# LED-PCB_DIG2.net
KiCad netlist of a schematic drawn in Altium Designer
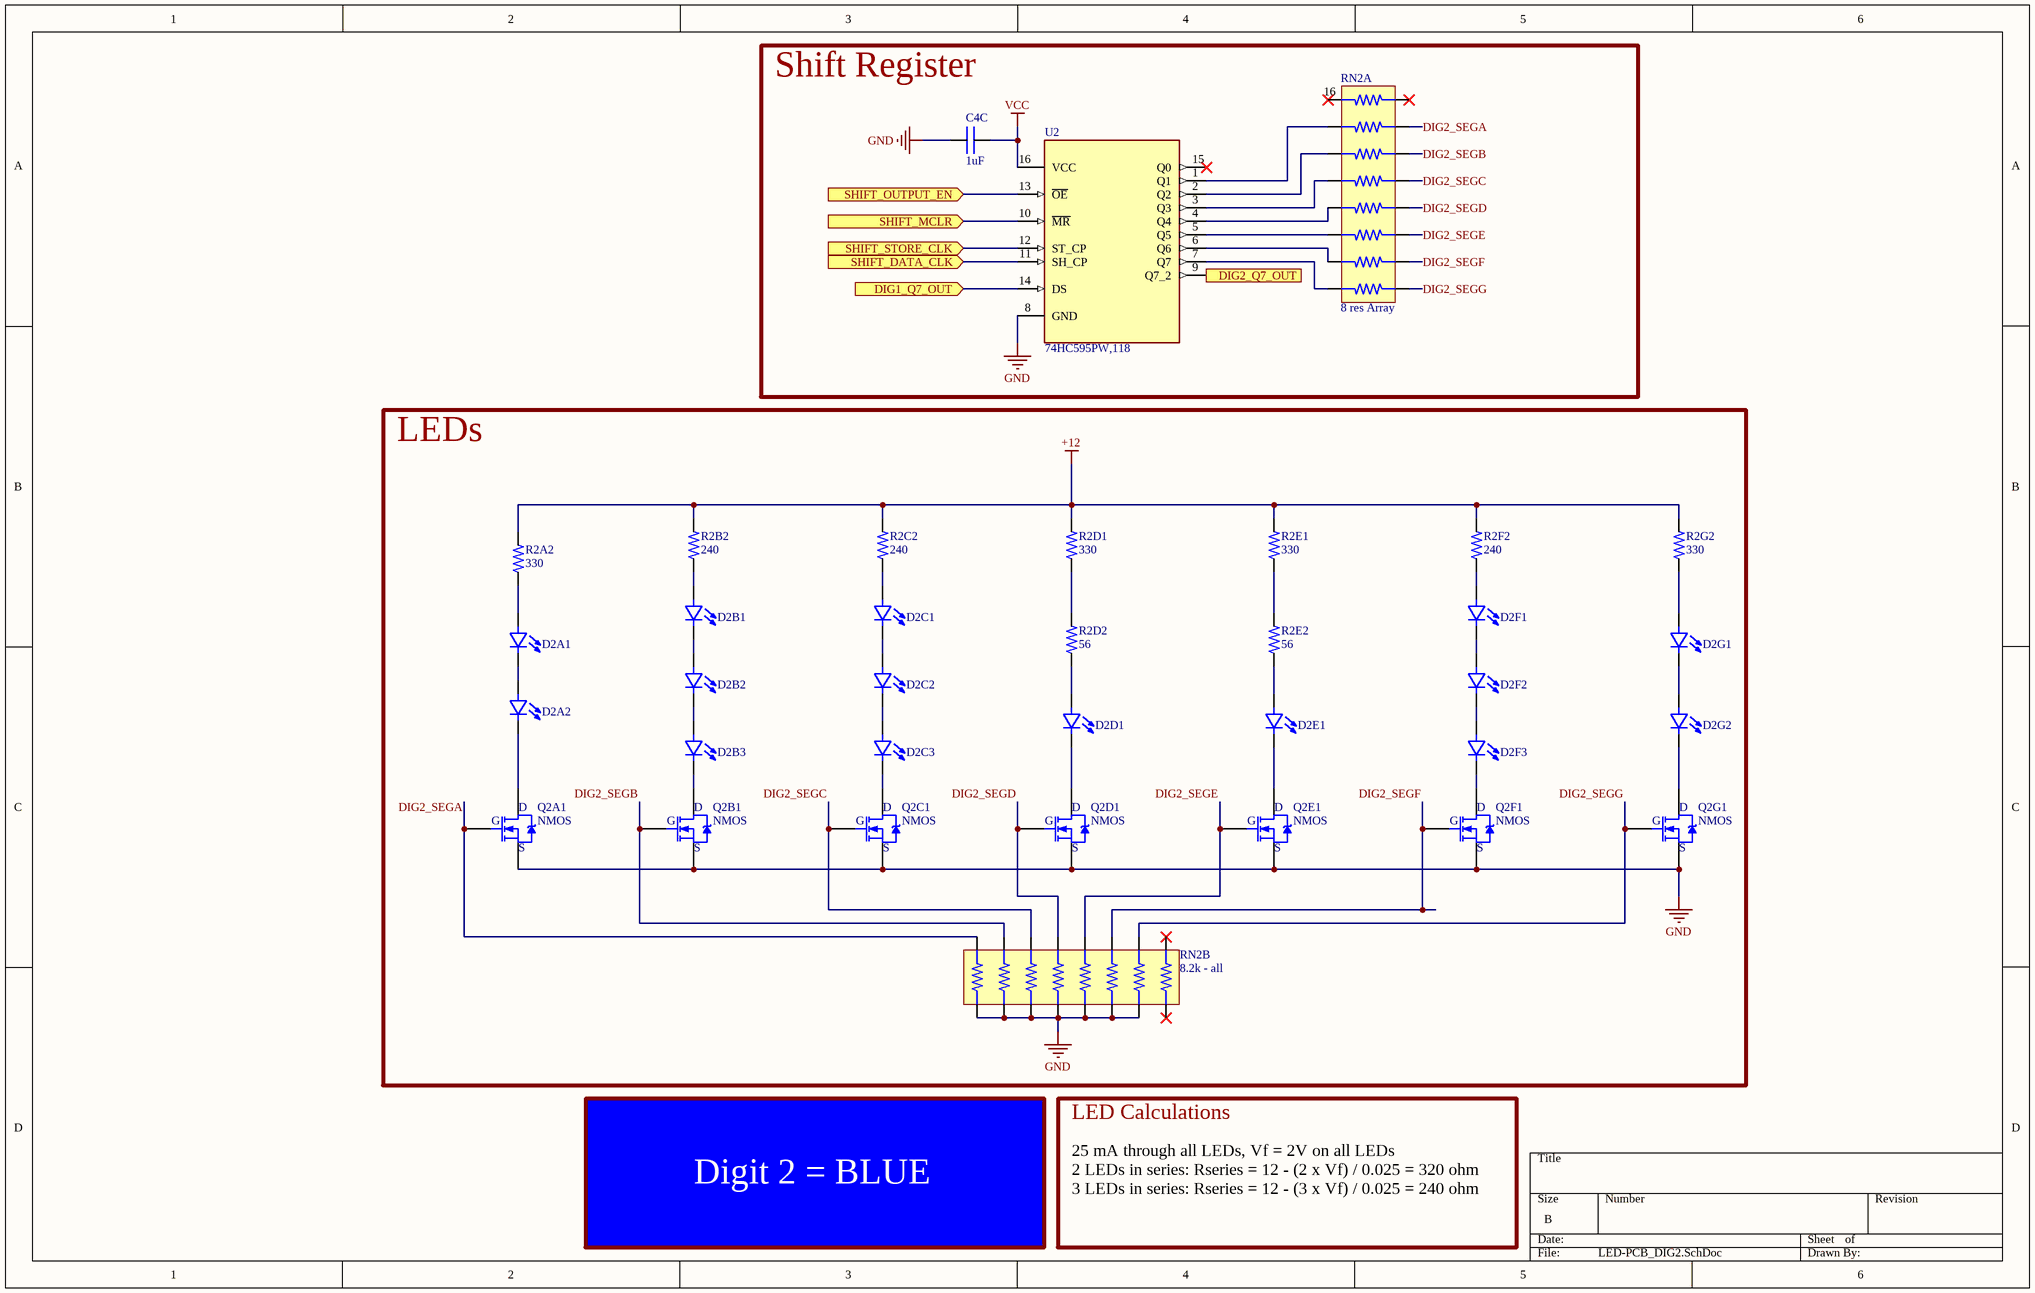
[diagram p0: LED-PCB_DIG2.SchDoc]

(export (version "E")
  (design (tool "Eeschema 10.0.6"))
  (components
    (comp (ref "C4C")
      (value "1uF")
      (footprint "sinking-clock:0402 CAP")
      (description "Capaicitor")
      (fields (field (name "MFR") "Samsung Microelectronics") (field (name "Comment") "CAP"))
      (libsource (lib "sinking-clock") (part "CAP"))
    )
    (comp (ref "D2A1")
      (value "LED - single")
      (footprint "sinking-clock:LED - 0603")
      (fields (field (name "MFR") "Wurth Elektronik"))
      (libsource (lib "sinking-clock") (part "LED - single"))
    )
    (comp (ref "D2A2")
      (value "LED - single")
      (footprint "sinking-clock:LED - 0603")
      (fields (field (name "MFR") "Wurth Elektronik"))
      (libsource (lib "sinking-clock") (part "LED - single"))
    )
    (comp (ref "D2B1")
      (value "LED - single")
      (footprint "sinking-clock:LED - 0603")
      (fields (field (name "MFR") "Wurth Elektronik"))
      (libsource (lib "sinking-clock") (part "LED - single"))
    )
    (comp (ref "D2B2")
      (value "LED - single")
      (footprint "sinking-clock:LED - 0603")
      (fields (field (name "MFR") "Wurth Elektronik"))
      (libsource (lib "sinking-clock") (part "LED - single"))
    )
    (comp (ref "D2B3")
      (value "LED - single")
      (footprint "sinking-clock:LED - 0603")
      (fields (field (name "MFR") "Wurth Elektronik"))
      (libsource (lib "sinking-clock") (part "LED - single"))
    )
    (comp (ref "D2C1")
      (value "LED - single")
      (footprint "sinking-clock:LED - 0603")
      (fields (field (name "MFR") "Wurth Elektronik"))
      (libsource (lib "sinking-clock") (part "LED - single"))
    )
    (comp (ref "D2C2")
      (value "LED - single")
      (footprint "sinking-clock:LED - 0603")
      (fields (field (name "MFR") "Wurth Elektronik"))
      (libsource (lib "sinking-clock") (part "LED - single"))
    )
    (comp (ref "D2C3")
      (value "LED - single")
      (footprint "sinking-clock:LED - 0603")
      (fields (field (name "MFR") "Wurth Elektronik"))
      (libsource (lib "sinking-clock") (part "LED - single"))
    )
    (comp (ref "D2D1")
      (value "LED - single")
      (footprint "sinking-clock:LED - 0603")
      (fields (field (name "MFR") "Wurth Elektronik"))
      (libsource (lib "sinking-clock") (part "LED - single"))
    )
    (comp (ref "D2E1")
      (value "LED - single")
      (footprint "sinking-clock:LED - 0603")
      (fields (field (name "MFR") "Wurth Elektronik"))
      (libsource (lib "sinking-clock") (part "LED - single"))
    )
    (comp (ref "D2F1")
      (value "LED - single")
      (footprint "sinking-clock:LED - 0603")
      (fields (field (name "MFR") "Wurth Elektronik"))
      (libsource (lib "sinking-clock") (part "LED - single"))
    )
    (comp (ref "D2F2")
      (value "LED - single")
      (footprint "sinking-clock:LED - 0603")
      (fields (field (name "MFR") "Wurth Elektronik"))
      (libsource (lib "sinking-clock") (part "LED - single"))
    )
    (comp (ref "D2F3")
      (value "LED - single")
      (footprint "sinking-clock:LED - 0603")
      (fields (field (name "MFR") "Wurth Elektronik"))
      (libsource (lib "sinking-clock") (part "LED - single"))
    )
    (comp (ref "D2G1")
      (value "LED - single")
      (footprint "sinking-clock:LED - 0603")
      (fields (field (name "MFR") "Wurth Elektronik"))
      (libsource (lib "sinking-clock") (part "LED - single"))
    )
    (comp (ref "D2G2")
      (value "LED - single")
      (footprint "sinking-clock:LED - 0603")
      (fields (field (name "MFR") "Wurth Elektronik"))
      (libsource (lib "sinking-clock") (part "LED - single"))
    )
    (comp (ref "Q2A1")
      (value "NMOS")
      (footprint "sinking-clock:SOT-23")
      (description "N-Channel MOSFET")
      (fields (field (name "MFR") "Diodes Incorporated"))
      (libsource (lib "sinking-clock") (part "NMOS"))
    )
    (comp (ref "Q2B1")
      (value "NMOS")
      (footprint "sinking-clock:SOT-23")
      (description "N-Channel MOSFET")
      (fields (field (name "MFR") "Diodes Incorporated"))
      (libsource (lib "sinking-clock") (part "NMOS"))
    )
    (comp (ref "Q2C1")
      (value "NMOS")
      (footprint "sinking-clock:SOT-23")
      (description "N-Channel MOSFET")
      (fields (field (name "MFR") "Diodes Incorporated"))
      (libsource (lib "sinking-clock") (part "NMOS"))
    )
    (comp (ref "Q2D1")
      (value "NMOS")
      (footprint "sinking-clock:SOT-23")
      (description "N-Channel MOSFET")
      (fields (field (name "MFR") "Diodes Incorporated"))
      (libsource (lib "sinking-clock") (part "NMOS"))
    )
    (comp (ref "Q2E1")
      (value "NMOS")
      (footprint "sinking-clock:SOT-23")
      (description "N-Channel MOSFET")
      (fields (field (name "MFR") "Diodes Incorporated"))
      (libsource (lib "sinking-clock") (part "NMOS"))
    )
    (comp (ref "Q2F1")
      (value "NMOS")
      (footprint "sinking-clock:SOT-23")
      (description "N-Channel MOSFET")
      (fields (field (name "MFR") "Diodes Incorporated"))
      (libsource (lib "sinking-clock") (part "NMOS"))
    )
    (comp (ref "Q2G1")
      (value "NMOS")
      (footprint "sinking-clock:SOT-23")
      (description "N-Channel MOSFET")
      (fields (field (name "MFR") "Diodes Incorporated"))
      (libsource (lib "sinking-clock") (part "NMOS"))
    )
    (comp (ref "R2A2")
      (value "330")
      (footprint "sinking-clock:0402 RES")
      (description "Resistor")
      (fields (field (name "MFR") "YAGEO") (field (name "Comment") "RES"))
      (libsource (lib "sinking-clock") (part "RES"))
    )
    (comp (ref "R2B2")
      (value "240")
      (footprint "sinking-clock:0402 RES")
      (description "Resistor")
      (fields (field (name "MFR") "YAGEO") (field (name "Comment") "RES"))
      (libsource (lib "sinking-clock") (part "RES"))
    )
    (comp (ref "R2C2")
      (value "240")
      (footprint "sinking-clock:0402 RES")
      (description "Resistor")
      (fields (field (name "MFR") "YAGEO") (field (name "Comment") "RES"))
      (libsource (lib "sinking-clock") (part "RES"))
    )
    (comp (ref "R2D1")
      (value "330")
      (footprint "sinking-clock:0402 RES")
      (description "Resistor")
      (fields (field (name "MFR") "YAGEO") (field (name "Comment") "RES"))
      (libsource (lib "sinking-clock") (part "RES"))
    )
    (comp (ref "R2D2")
      (value "56")
      (footprint "sinking-clock:0402 RES")
      (description "Resistor")
      (fields (field (name "MFR") "YAGEO") (field (name "Comment") "RES"))
      (libsource (lib "sinking-clock") (part "RES"))
    )
    (comp (ref "R2E1")
      (value "330")
      (footprint "sinking-clock:0402 RES")
      (description "Resistor")
      (fields (field (name "MFR") "YAGEO") (field (name "Comment") "RES"))
      (libsource (lib "sinking-clock") (part "RES"))
    )
    (comp (ref "R2E2")
      (value "56")
      (footprint "sinking-clock:0402 RES")
      (description "Resistor")
      (fields (field (name "MFR") "YAGEO") (field (name "Comment") "RES"))
      (libsource (lib "sinking-clock") (part "RES"))
    )
    (comp (ref "R2F2")
      (value "240")
      (footprint "sinking-clock:0402 RES")
      (description "Resistor")
      (fields (field (name "MFR") "YAGEO") (field (name "Comment") "RES"))
      (libsource (lib "sinking-clock") (part "RES"))
    )
    (comp (ref "R2G2")
      (value "330")
      (footprint "sinking-clock:0402 RES")
      (description "Resistor")
      (fields (field (name "MFR") "YAGEO") (field (name "Comment") "RES"))
      (libsource (lib "sinking-clock") (part "RES"))
    )
    (comp (ref "RN2A")
      (value "8 res Array")
      (footprint "sinking-clock:EXB2HV331JV")
      (fields (field (name "MFR") "Panasonic Microelectronics"))
      (libsource (lib "sinking-clock") (part "8 res Array"))
    )
    (comp (ref "RN2B")
      (value "8.2k - all")
      (footprint "sinking-clock:MNR18ERAPJ822")
      (fields (field (name "MFR") "Rohm Semiconductor"))
      (libsource (lib "sinking-clock") (part "MNR18ERAPJ822"))
    )
    (comp (ref "U2")
      (value "74HC595PW,118")
      (footprint "sinking-clock:16-TSSOP")
      (description "Shift Shift Register 1 Element 8 Bit 16-TSSOP")
      (libsource (lib "sinking-clock") (part "74HC595PW,118"))
    )
  )
  (nets
    (net (code "1") (name "+12") (class "Default")
      (node (ref "R2A2") (pin "2") (pinfunction "2_2") (pintype "passive"))
      (node (ref "R2B2") (pin "2") (pinfunction "2_2") (pintype "passive"))
      (node (ref "R2C2") (pin "2") (pinfunction "2_2") (pintype "passive"))
      (node (ref "R2D1") (pin "2") (pinfunction "2_2") (pintype "passive"))
      (node (ref "R2E1") (pin "2") (pinfunction "2_2") (pintype "passive"))
      (node (ref "R2F2") (pin "2") (pinfunction "2_2") (pintype "passive"))
      (node (ref "R2G2") (pin "2") (pinfunction "2_2") (pintype "passive"))
    )
    (net (code "2") (name "/DIG1_Q7_OUT") (class "Default")
      (node (ref "U2") (pin "14") (pinfunction "DS_14") (pintype "input"))
    )
    (net (code "3") (name "/DIG2_Q7_OUT") (class "Default")
      (node (ref "U2") (pin "9") (pinfunction "Q7_2_9") (pintype "output"))
    )
    (net (code "4") (name "/DIG2_SEGA") (class "Default")
      (node (ref "Q2A1") (pin "1") (pinfunction "G_1") (pintype "passive"))
      (node (ref "RN2A") (pin "2") (pinfunction "2_2") (pintype "passive"))
      (node (ref "RN2B") (pin "16") (pinfunction "16_16") (pintype "passive"))
    )
    (net (code "5") (name "/DIG2_SEGB") (class "Default")
      (node (ref "Q2B1") (pin "1") (pinfunction "G_1") (pintype "passive"))
      (node (ref "RN2A") (pin "3") (pinfunction "3_3") (pintype "passive"))
      (node (ref "RN2B") (pin "15") (pinfunction "15_15") (pintype "passive"))
    )
    (net (code "6") (name "/DIG2_SEGC") (class "Default")
      (node (ref "Q2C1") (pin "1") (pinfunction "G_1") (pintype "passive"))
      (node (ref "RN2A") (pin "4") (pinfunction "4_4") (pintype "passive"))
      (node (ref "RN2B") (pin "14") (pinfunction "14_14") (pintype "passive"))
    )
    (net (code "7") (name "/DIG2_SEGD") (class "Default")
      (node (ref "Q2D1") (pin "1") (pinfunction "G_1") (pintype "passive"))
      (node (ref "RN2A") (pin "5") (pinfunction "5_5") (pintype "passive"))
      (node (ref "RN2B") (pin "13") (pinfunction "13_13") (pintype "passive"))
    )
    (net (code "8") (name "/DIG2_SEGE") (class "Default")
      (node (ref "Q2E1") (pin "1") (pinfunction "G_1") (pintype "passive"))
      (node (ref "RN2A") (pin "6") (pinfunction "6_6") (pintype "passive"))
      (node (ref "RN2B") (pin "12") (pinfunction "12_12") (pintype "passive"))
    )
    (net (code "9") (name "/DIG2_SEGF") (class "Default")
      (node (ref "Q2F1") (pin "1") (pinfunction "G_1") (pintype "passive"))
      (node (ref "RN2A") (pin "7") (pinfunction "7_7") (pintype "passive"))
      (node (ref "RN2B") (pin "11") (pinfunction "11_11") (pintype "passive"))
    )
    (net (code "10") (name "/DIG2_SEGG") (class "Default")
      (node (ref "Q2G1") (pin "1") (pinfunction "G_1") (pintype "passive"))
      (node (ref "RN2A") (pin "8") (pinfunction "8_8") (pintype "passive"))
      (node (ref "RN2B") (pin "10") (pinfunction "10_10") (pintype "passive"))
    )
    (net (code "11") (name "/SHIFT_DATA_CLK") (class "Default")
      (node (ref "U2") (pin "11") (pinfunction "SH_CP_11") (pintype "input"))
    )
    (net (code "12") (name "/SHIFT_MCLR") (class "Default")
      (node (ref "U2") (pin "10") (pinfunction "~{MR}_10") (pintype "input"))
    )
    (net (code "13") (name "/SHIFT_OUTPUT_EN") (class "Default")
      (node (ref "U2") (pin "13") (pinfunction "~{OE}_13") (pintype "input"))
    )
    (net (code "14") (name "/SHIFT_STORE_CLK") (class "Default")
      (node (ref "U2") (pin "12") (pinfunction "ST_CP_12") (pintype "input"))
    )
    (net (code "15") (name "GND") (class "Default")
      (node (ref "C4C") (pin "1") (pinfunction "1_1") (pintype "passive"))
      (node (ref "Q2A1") (pin "2") (pinfunction "S_2") (pintype "passive"))
      (node (ref "Q2B1") (pin "2") (pinfunction "S_2") (pintype "passive"))
      (node (ref "Q2C1") (pin "2") (pinfunction "S_2") (pintype "passive"))
      (node (ref "Q2D1") (pin "2") (pinfunction "S_2") (pintype "passive"))
      (node (ref "Q2E1") (pin "2") (pinfunction "S_2") (pintype "passive"))
      (node (ref "Q2F1") (pin "2") (pinfunction "S_2") (pintype "passive"))
      (node (ref "Q2G1") (pin "2") (pinfunction "S_2") (pintype "passive"))
      (node (ref "RN2B") (pin "1") (pinfunction "1_1") (pintype "passive"))
      (node (ref "RN2B") (pin "2") (pinfunction "2_2") (pintype "passive"))
      (node (ref "RN2B") (pin "3") (pinfunction "3_3") (pintype "passive"))
      (node (ref "RN2B") (pin "4") (pinfunction "4_4") (pintype "passive"))
      (node (ref "RN2B") (pin "5") (pinfunction "5_5") (pintype "passive"))
      (node (ref "RN2B") (pin "6") (pinfunction "6_6") (pintype "passive"))
      (node (ref "RN2B") (pin "7") (pinfunction "7_7") (pintype "passive"))
      (node (ref "U2") (pin "8") (pinfunction "GND_8") (pintype "passive"))
    )
    (net (code "16") (name "Net-(D2A1-A)") (class "Default")
      (node (ref "D2A1") (pin "1") (pinfunction "A_1") (pintype "passive"))
      (node (ref "R2A2") (pin "1") (pinfunction "1_1") (pintype "passive"))
    )
    (net (code "17") (name "Net-(D2A1-C)") (class "Default")
      (node (ref "D2A1") (pin "2") (pinfunction "C_2") (pintype "passive"))
      (node (ref "D2A2") (pin "1") (pinfunction "A_1") (pintype "passive"))
    )
    (net (code "18") (name "Net-(D2A2-C)") (class "Default")
      (node (ref "D2A2") (pin "2") (pinfunction "C_2") (pintype "passive"))
      (node (ref "Q2A1") (pin "3") (pinfunction "D_3") (pintype "passive"))
    )
    (net (code "19") (name "Net-(D2B1-A)") (class "Default")
      (node (ref "D2B1") (pin "1") (pinfunction "A_1") (pintype "passive"))
      (node (ref "R2B2") (pin "1") (pinfunction "1_1") (pintype "passive"))
    )
    (net (code "20") (name "Net-(D2B1-C)") (class "Default")
      (node (ref "D2B1") (pin "2") (pinfunction "C_2") (pintype "passive"))
      (node (ref "D2B2") (pin "1") (pinfunction "A_1") (pintype "passive"))
    )
    (net (code "21") (name "Net-(D2B2-C)") (class "Default")
      (node (ref "D2B2") (pin "2") (pinfunction "C_2") (pintype "passive"))
      (node (ref "D2B3") (pin "1") (pinfunction "A_1") (pintype "passive"))
    )
    (net (code "22") (name "Net-(D2B3-C)") (class "Default")
      (node (ref "D2B3") (pin "2") (pinfunction "C_2") (pintype "passive"))
      (node (ref "Q2B1") (pin "3") (pinfunction "D_3") (pintype "passive"))
    )
    (net (code "23") (name "Net-(D2C1-A)") (class "Default")
      (node (ref "D2C1") (pin "1") (pinfunction "A_1") (pintype "passive"))
      (node (ref "R2C2") (pin "1") (pinfunction "1_1") (pintype "passive"))
    )
    (net (code "24") (name "Net-(D2C1-C)") (class "Default")
      (node (ref "D2C1") (pin "2") (pinfunction "C_2") (pintype "passive"))
      (node (ref "D2C2") (pin "1") (pinfunction "A_1") (pintype "passive"))
    )
    (net (code "25") (name "Net-(D2C2-C)") (class "Default")
      (node (ref "D2C2") (pin "2") (pinfunction "C_2") (pintype "passive"))
      (node (ref "D2C3") (pin "1") (pinfunction "A_1") (pintype "passive"))
    )
    (net (code "26") (name "Net-(D2C3-C)") (class "Default")
      (node (ref "D2C3") (pin "2") (pinfunction "C_2") (pintype "passive"))
      (node (ref "Q2C1") (pin "3") (pinfunction "D_3") (pintype "passive"))
    )
    (net (code "27") (name "Net-(D2D1-A)") (class "Default")
      (node (ref "D2D1") (pin "1") (pinfunction "A_1") (pintype "passive"))
      (node (ref "R2D2") (pin "1") (pinfunction "1_1") (pintype "passive"))
    )
    (net (code "28") (name "Net-(D2D1-C)") (class "Default")
      (node (ref "D2D1") (pin "2") (pinfunction "C_2") (pintype "passive"))
      (node (ref "Q2D1") (pin "3") (pinfunction "D_3") (pintype "passive"))
    )
    (net (code "29") (name "Net-(D2E1-A)") (class "Default")
      (node (ref "D2E1") (pin "1") (pinfunction "A_1") (pintype "passive"))
      (node (ref "R2E2") (pin "1") (pinfunction "1_1") (pintype "passive"))
    )
    (net (code "30") (name "Net-(D2E1-C)") (class "Default")
      (node (ref "D2E1") (pin "2") (pinfunction "C_2") (pintype "passive"))
      (node (ref "Q2E1") (pin "3") (pinfunction "D_3") (pintype "passive"))
    )
    (net (code "31") (name "Net-(D2F1-A)") (class "Default")
      (node (ref "D2F1") (pin "1") (pinfunction "A_1") (pintype "passive"))
      (node (ref "R2F2") (pin "1") (pinfunction "1_1") (pintype "passive"))
    )
    (net (code "32") (name "Net-(D2F1-C)") (class "Default")
      (node (ref "D2F1") (pin "2") (pinfunction "C_2") (pintype "passive"))
      (node (ref "D2F2") (pin "1") (pinfunction "A_1") (pintype "passive"))
    )
    (net (code "33") (name "Net-(D2F2-C)") (class "Default")
      (node (ref "D2F2") (pin "2") (pinfunction "C_2") (pintype "passive"))
      (node (ref "D2F3") (pin "1") (pinfunction "A_1") (pintype "passive"))
    )
    (net (code "34") (name "Net-(D2F3-C)") (class "Default")
      (node (ref "D2F3") (pin "2") (pinfunction "C_2") (pintype "passive"))
      (node (ref "Q2F1") (pin "3") (pinfunction "D_3") (pintype "passive"))
    )
    (net (code "35") (name "Net-(D2G1-A)") (class "Default")
      (node (ref "D2G1") (pin "1") (pinfunction "A_1") (pintype "passive"))
      (node (ref "R2G2") (pin "1") (pinfunction "1_1") (pintype "passive"))
    )
    (net (code "36") (name "Net-(D2G1-C)") (class "Default")
      (node (ref "D2G1") (pin "2") (pinfunction "C_2") (pintype "passive"))
      (node (ref "D2G2") (pin "1") (pinfunction "A_1") (pintype "passive"))
    )
    (net (code "37") (name "Net-(D2G2-C)") (class "Default")
      (node (ref "D2G2") (pin "2") (pinfunction "C_2") (pintype "passive"))
      (node (ref "Q2G1") (pin "3") (pinfunction "D_3") (pintype "passive"))
    )
    (net (code "38") (name "Net-(R2D1-Pad1)") (class "Default")
      (node (ref "R2D1") (pin "1") (pinfunction "1_1") (pintype "passive"))
      (node (ref "R2D2") (pin "2") (pinfunction "2_2") (pintype "passive"))
    )
    (net (code "39") (name "Net-(R2E1-Pad1)") (class "Default")
      (node (ref "R2E1") (pin "1") (pinfunction "1_1") (pintype "passive"))
      (node (ref "R2E2") (pin "2") (pinfunction "2_2") (pintype "passive"))
    )
    (net (code "40") (name "Net-(U2-Q1)") (class "Default")
      (node (ref "RN2A") (pin "15") (pinfunction "15_15") (pintype "passive"))
      (node (ref "U2") (pin "1") (pinfunction "Q1_1") (pintype "output"))
    )
    (net (code "41") (name "Net-(U2-Q2)") (class "Default")
      (node (ref "RN2A") (pin "14") (pinfunction "14_14") (pintype "passive"))
      (node (ref "U2") (pin "2") (pinfunction "Q2_2") (pintype "output"))
    )
    (net (code "42") (name "Net-(U2-Q3)") (class "Default")
      (node (ref "RN2A") (pin "13") (pinfunction "13_13") (pintype "passive"))
      (node (ref "U2") (pin "3") (pinfunction "Q3_3") (pintype "output"))
    )
    (net (code "43") (name "Net-(U2-Q4)") (class "Default")
      (node (ref "RN2A") (pin "12") (pinfunction "12_12") (pintype "passive"))
      (node (ref "U2") (pin "4") (pinfunction "Q4_4") (pintype "output"))
    )
    (net (code "44") (name "Net-(U2-Q5)") (class "Default")
      (node (ref "RN2A") (pin "11") (pinfunction "11_11") (pintype "passive"))
      (node (ref "U2") (pin "5") (pinfunction "Q5_5") (pintype "output"))
    )
    (net (code "45") (name "Net-(U2-Q6)") (class "Default")
      (node (ref "RN2A") (pin "10") (pinfunction "10_10") (pintype "passive"))
      (node (ref "U2") (pin "6") (pinfunction "Q6_6") (pintype "output"))
    )
    (net (code "46") (name "Net-(U2-Q7)") (class "Default")
      (node (ref "RN2A") (pin "9") (pinfunction "9_9") (pintype "passive"))
      (node (ref "U2") (pin "7") (pinfunction "Q7_7") (pintype "output"))
    )
    (net (code "47") (name "VCC") (class "Default")
      (node (ref "C4C") (pin "2") (pinfunction "2_2") (pintype "passive"))
      (node (ref "U2") (pin "16") (pinfunction "VCC_16") (pintype "power_in"))
    )
    (net (code "48") (name "unconnected-(RN2A-Pad1)") (class "Default")
      (node (ref "RN2A") (pin "1") (pinfunction "1_1") (pintype "passive+no_connect"))
    )
    (net (code "49") (name "unconnected-(RN2A-Pad16)") (class "Default")
      (node (ref "RN2A") (pin "16") (pinfunction "16_16") (pintype "passive+no_connect"))
    )
    (net (code "50") (name "unconnected-(RN2B-Pad8)") (class "Default")
      (node (ref "RN2B") (pin "8") (pinfunction "8_8") (pintype "passive+no_connect"))
    )
    (net (code "51") (name "unconnected-(RN2B-Pad9)") (class "Default")
      (node (ref "RN2B") (pin "9") (pinfunction "9_9") (pintype "passive+no_connect"))
    )
    (net (code "52") (name "unconnected-(U2-Q0-Pad15)") (class "Default")
      (node (ref "U2") (pin "15") (pinfunction "Q0_15") (pintype "output+no_connect"))
    )
  )
)
